# Drone.net
KiCad netlist of a schematic drawn in Altium Designer
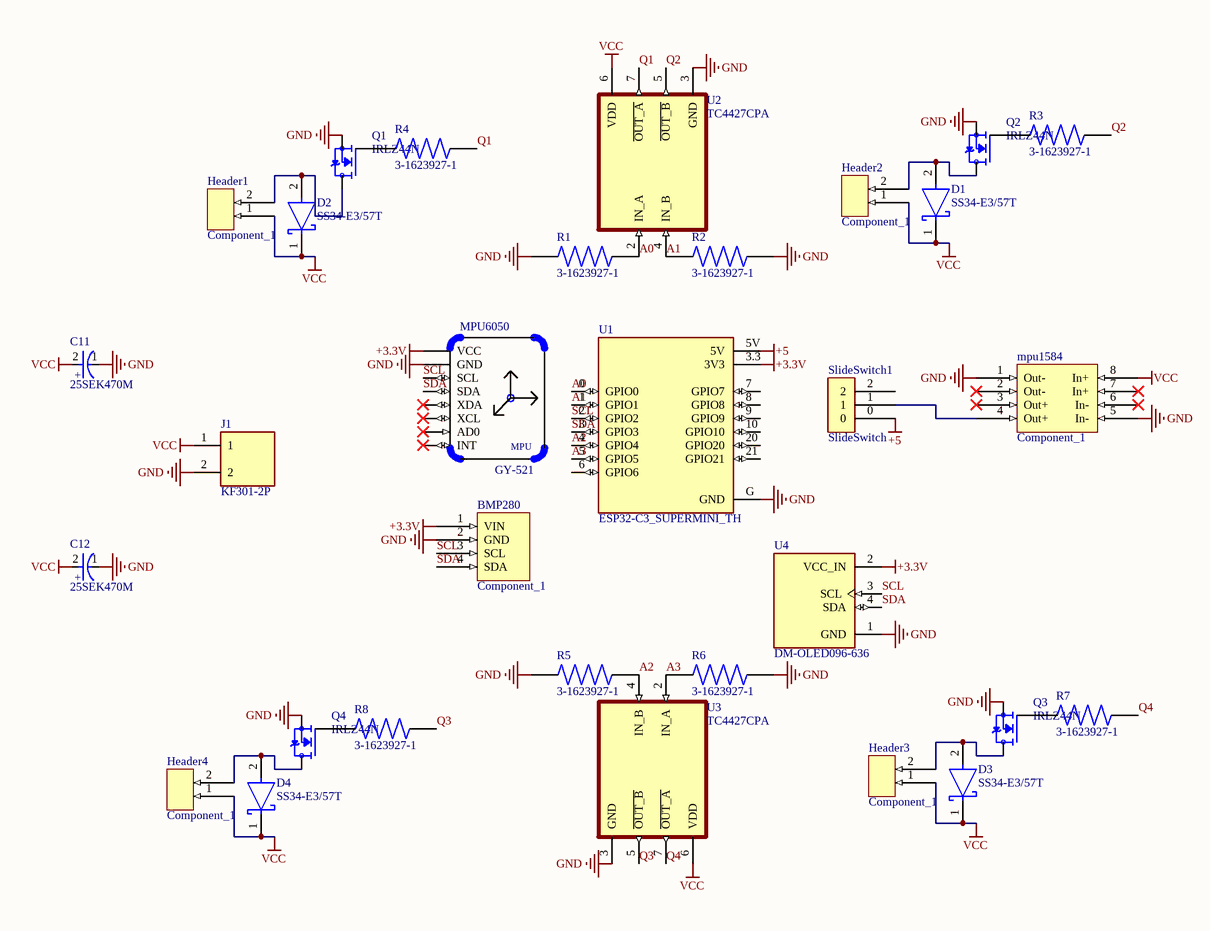
[diagram p0: Drone.SchDoc]

(export (version "E")
  (design (tool "Eeschema 10.0.6"))
  (components
    (comp (ref "BMP280")
      (value "Component_1")
      (footprint "PCBComponent_1")
      (libsource (lib "BMP280_4Pin_5V") (part "Component_1"))
    )
    (comp (ref "C11")
      (value "25SEK470M")
      (footprint "FP-OS-CON-TH-F13-d_0_6-MFG")
      (description "Conductive Polymer Aluminum Solid Capacitors (OS-CON) 470uF ±20% 25V RADIAL TH 10x13mm")
      (libsource (lib "470uF_aluminum") (part "CMP-05428-000411-1"))
    )
    (comp (ref "C12")
      (value "25SEK470M")
      (footprint "FP-OS-CON-TH-F13-d_0_6-MFG")
      (description "Conductive Polymer Aluminum Solid Capacitors (OS-CON) 470uF ±20% 25V RADIAL TH 10x13mm")
      (libsource (lib "470uF_aluminum") (part "CMP-05428-000411-1"))
    )
    (comp (ref "D1")
      (value "SS34-E3/57T")
      (footprint "FP-95402-MFG")
      (description "DIODE SCHOTTKY 40V 3A DO214AB")
      (fields
        (field (name "MANUFACTURER") "Vishay")
        (field (name "OCTOPART") "https://octopart.com/ss34-e3%2F57t-vishay-39552907")
      )
      (libsource (lib "SS34") (part "CMP-02539-000012-1"))
    )
    (comp (ref "D2")
      (value "SS34-E3/57T")
      (footprint "FP-95402-MFG")
      (description "DIODE SCHOTTKY 40V 3A DO214AB")
      (fields
        (field (name "MANUFACTURER") "Vishay")
        (field (name "OCTOPART") "https://octopart.com/ss34-e3%2F57t-vishay-39552907")
      )
      (libsource (lib "SS34") (part "CMP-02539-000012-1"))
    )
    (comp (ref "D3")
      (value "SS34-E3/57T")
      (footprint "FP-95402-MFG")
      (description "DIODE SCHOTTKY 40V 3A DO214AB")
      (fields
        (field (name "MANUFACTURER") "Vishay")
        (field (name "OCTOPART") "https://octopart.com/ss34-e3%2F57t-vishay-39552907")
      )
      (libsource (lib "SS34") (part "CMP-02539-000012-1"))
    )
    (comp (ref "D4")
      (value "SS34-E3/57T")
      (footprint "FP-95402-MFG")
      (description "DIODE SCHOTTKY 40V 3A DO214AB")
      (fields
        (field (name "MANUFACTURER") "Vishay")
        (field (name "OCTOPART") "https://octopart.com/ss34-e3%2F57t-vishay-39552907")
      )
      (libsource (lib "SS34") (part "CMP-02539-000012-1"))
    )
    (comp (ref "Header1")
      (value "Component_1")
      (footprint "1X2P")
      (libsource (lib "1X2P") (part "Component_1"))
    )
    (comp (ref "Header2")
      (value "Component_1")
      (footprint "1X2P")
      (libsource (lib "1X2P") (part "Component_1"))
    )
    (comp (ref "Header3")
      (value "Component_1")
      (footprint "1X2P")
      (libsource (lib "1X2P") (part "Component_1"))
    )
    (comp (ref "Header4")
      (value "Component_1")
      (footprint "1X2P")
      (libsource (lib "1X2P") (part "Component_1"))
    )
    (comp (ref "J1")
      (value "KF301-2P")
      (footprint "HANDSON_KF301-2P")
      (description "2 Pin Terminal Block 5mm Pitch")
      (fields (field (name "MF") "Handson Technology"))
      (libsource (lib "Header_2_foot") (part "KF301-2P"))
    )
    (comp (ref "mpu1584")
      (value "Component_1")
      (footprint "PCBComponent_1")
      (libsource (lib "mpu1584_module") (part "Component_1"))
    )
    (comp (ref "MPU6050")
      (value "GY-521")
      (footprint "*GY-521_GY-521(Primary)")
      (description "Triple Axis Accelerometer Gyro Breakout")
      (fields (field (name "MF") "GODREAM FORDREAM CO., LIMITED"))
      (libsource (lib "GY-521") (part "GY-521"))
    )
    (comp (ref "Q1")
      (value "IRLZ44N")
      (footprint "TO254P1054X469X1930-3")
      (description "N-Channel 55 V 47A (Tc) 3.8W (Ta), 110W (Tc) Surface Mount D2PAK")
      (fields (field (name "MF") "Infineon / IR"))
      (libsource (lib "IRLZ44N") (part "IRLZ44N"))
    )
    (comp (ref "Q2")
      (value "IRLZ44N")
      (footprint "TO254P1054X469X1930-3")
      (description "N-Channel 55 V 47A (Tc) 3.8W (Ta), 110W (Tc) Surface Mount D2PAK")
      (fields (field (name "MF") "Infineon / IR"))
      (libsource (lib "IRLZ44N") (part "IRLZ44N"))
    )
    (comp (ref "Q3")
      (value "IRLZ44N")
      (footprint "TO254P1054X469X1930-3")
      (description "N-Channel 55 V 47A (Tc) 3.8W (Ta), 110W (Tc) Surface Mount D2PAK")
      (fields (field (name "MF") "Infineon / IR"))
      (libsource (lib "IRLZ44N") (part "IRLZ44N"))
    )
    (comp (ref "Q4")
      (value "IRLZ44N")
      (footprint "TO254P1054X469X1930-3")
      (description "N-Channel 55 V 47A (Tc) 3.8W (Ta), 110W (Tc) Surface Mount D2PAK")
      (fields (field (name "MF") "Infineon / IR"))
      (libsource (lib "IRLZ44N") (part "IRLZ44N"))
    )
    (comp (ref "R1")
      (value "3-1623927-1")
      (footprint "RESAD700W45L350D185")
      (description "1 MOhms Â±5% 0.25W, 1/4W Through Hole Resistor Axial - Carbon Film")
      (fields (field (name "MF") "TE Connectivity"))
      (libsource (lib "3-1623927-1-res-plug") (part "3-1623927-1"))
    )
    (comp (ref "R2")
      (value "3-1623927-1")
      (footprint "RESAD700W45L350D185")
      (description "1 MOhms Â±5% 0.25W, 1/4W Through Hole Resistor Axial - Carbon Film")
      (fields (field (name "MF") "TE Connectivity"))
      (libsource (lib "3-1623927-1-res-plug") (part "3-1623927-1"))
    )
    (comp (ref "R3")
      (value "3-1623927-1")
      (footprint "RESAD700W45L350D185")
      (description "1 MOhms Â±5% 0.25W, 1/4W Through Hole Resistor Axial - Carbon Film")
      (fields (field (name "MF") "TE Connectivity"))
      (libsource (lib "3-1623927-1-res-plug") (part "3-1623927-1"))
    )
    (comp (ref "R4")
      (value "3-1623927-1")
      (footprint "RESAD700W45L350D185")
      (description "1 MOhms Â±5% 0.25W, 1/4W Through Hole Resistor Axial - Carbon Film")
      (fields (field (name "MF") "TE Connectivity"))
      (libsource (lib "3-1623927-1-res-plug") (part "3-1623927-1"))
    )
    (comp (ref "R5")
      (value "3-1623927-1")
      (footprint "RESAD700W45L350D185")
      (description "1 MOhms Â±5% 0.25W, 1/4W Through Hole Resistor Axial - Carbon Film")
      (fields (field (name "MF") "TE Connectivity"))
      (libsource (lib "3-1623927-1-res-plug") (part "3-1623927-1"))
    )
    (comp (ref "R6")
      (value "3-1623927-1")
      (footprint "RESAD700W45L350D185")
      (description "1 MOhms Â±5% 0.25W, 1/4W Through Hole Resistor Axial - Carbon Film")
      (fields (field (name "MF") "TE Connectivity"))
      (libsource (lib "3-1623927-1-res-plug") (part "3-1623927-1"))
    )
    (comp (ref "R7")
      (value "3-1623927-1")
      (footprint "RESAD700W45L350D185")
      (description "1 MOhms Â±5% 0.25W, 1/4W Through Hole Resistor Axial - Carbon Film")
      (fields (field (name "MF") "TE Connectivity"))
      (libsource (lib "3-1623927-1-res-plug") (part "3-1623927-1"))
    )
    (comp (ref "R8")
      (value "3-1623927-1")
      (footprint "RESAD700W45L350D185")
      (description "1 MOhms Â±5% 0.25W, 1/4W Through Hole Resistor Axial - Carbon Film")
      (fields (field (name "MF") "TE Connectivity"))
      (libsource (lib "3-1623927-1-res-plug") (part "3-1623927-1"))
    )
    (comp (ref "SlideSwitch1")
      (value "SlideSwitch")
      (footprint "PCBComponent_1")
      (libsource (lib "SlideSwitch") (part "SlideSwitch"))
    )
    (comp (ref "U1")
      (value "ESP32-C3_SUPERMINI_TH")
      (footprint "MODULE_ESP32-C3_SUPERMINI_TH")
      (description "Super tiny ESP32-C3 board")
      (fields (field (name "MF") "Espressif Systems") (field (name "MP") "ESP32-C3 SuperMini_TH"))
      (libsource (lib "ESP32-C3_SUPERMINI_TH") (part "ESP32-C3_SUPERMINI_TH"))
    )
    (comp (ref "U2")
      (value "TC4427CPA")
      (footprint "DIP794W46P254L978H432Q8")
      (fields (field (name "MF") "Microchip Technology"))
      (libsource (lib "TC4427CPA") (part "TC4427CPA"))
    )
    (comp (ref "U3")
      (value "TC4427CPA")
      (footprint "DIP794W46P254L978H432Q8")
      (fields (field (name "MF") "Microchip Technology"))
      (libsource (lib "") (part "TC4427CPA_1"))
    )
    (comp (ref "U4")
      (value "DM-OLED096-636")
      (footprint "MODULE_DM-OLED096-636")
      (description "0.96â€ 128 X 64 MONOCHROME GRAPHIC OLED DISPLAY MODULE - I2C")
      (fields (field (name "MF") "Display Module"))
      (libsource (lib "DM-OLED096-636") (part "DM-OLED096-636"))
    )
  )
  (nets
    (net (code "1") (name "+3.3V") (class "Default")
      (node (ref "BMP280") (pin "1") (pinfunction "VIN_1") (pintype "input"))
      (node (ref "MPU6050") (pin "VCC") (pinfunction "VCC_VCC") (pintype "power_in"))
      (node (ref "U1") (pin "3.3") (pinfunction "3V3_3.3") (pintype "power_in"))
      (node (ref "U4") (pin "2") (pinfunction "VCC_IN_2") (pintype "power_in"))
    )
    (net (code "2") (name "+5") (class "Default")
      (node (ref "SlideSwitch1") (pin "0") (pinfunction "0_0") (pintype "passive"))
      (node (ref "U1") (pin "5V") (pinfunction "5V_5V") (pintype "power_in"))
    )
    (net (code "3") (name "/A0") (class "Default")
      (node (ref "R1") (pin "2") (pinfunction "2_2") (pintype "passive"))
      (node (ref "U1") (pin "0") (pinfunction "GPIO0_0") (pintype "bidirectional"))
      (node (ref "U2") (pin "2") (pinfunction "IN_A_2") (pintype "input"))
    )
    (net (code "4") (name "/A1") (class "Default")
      (node (ref "R2") (pin "1") (pinfunction "1_1") (pintype "passive"))
      (node (ref "U1") (pin "1") (pinfunction "GPIO1_1") (pintype "bidirectional"))
      (node (ref "U2") (pin "4") (pinfunction "IN_B_4") (pintype "input"))
    )
    (net (code "5") (name "/A2") (class "Default")
      (node (ref "R5") (pin "2") (pinfunction "2_2") (pintype "passive"))
      (node (ref "U1") (pin "4") (pinfunction "GPIO4_4") (pintype "bidirectional"))
      (node (ref "U3") (pin "4") (pinfunction "IN_B_4") (pintype "input"))
    )
    (net (code "6") (name "/A3") (class "Default")
      (node (ref "R6") (pin "1") (pinfunction "1_1") (pintype "passive"))
      (node (ref "U1") (pin "5") (pinfunction "GPIO5_5") (pintype "bidirectional"))
      (node (ref "U3") (pin "2") (pinfunction "IN_A_2") (pintype "input"))
    )
    (net (code "7") (name "/Q1") (class "Default")
      (node (ref "R4") (pin "2") (pinfunction "2_2") (pintype "passive"))
      (node (ref "U2") (pin "7") (pinfunction "~{OUT_A}_7") (pintype "output"))
    )
    (net (code "8") (name "/Q2") (class "Default")
      (node (ref "R3") (pin "2") (pinfunction "2_2") (pintype "passive"))
      (node (ref "U2") (pin "5") (pinfunction "~{OUT_B}_5") (pintype "output"))
    )
    (net (code "9") (name "/Q3") (class "Default")
      (node (ref "R8") (pin "2") (pinfunction "2_2") (pintype "passive"))
      (node (ref "U3") (pin "5") (pinfunction "~{OUT_B}_5") (pintype "output"))
    )
    (net (code "10") (name "/Q4") (class "Default")
      (node (ref "R7") (pin "2") (pinfunction "2_2") (pintype "passive"))
      (node (ref "U3") (pin "7") (pinfunction "~{OUT_A}_7") (pintype "output"))
    )
    (net (code "11") (name "/SCL") (class "Default")
      (node (ref "BMP280") (pin "3") (pinfunction "SCL_3") (pintype "input"))
      (node (ref "MPU6050") (pin "SCL") (pinfunction "SCL_SCL") (pintype "bidirectional"))
      (node (ref "U1") (pin "2") (pinfunction "GPIO2_2") (pintype "bidirectional"))
      (node (ref "U4") (pin "3") (pinfunction "SCL_3") (pintype "input"))
    )
    (net (code "12") (name "/SDA") (class "Default")
      (node (ref "BMP280") (pin "4") (pinfunction "SDA_4") (pintype "input"))
      (node (ref "MPU6050") (pin "SDA") (pinfunction "SDA_SDA") (pintype "bidirectional"))
      (node (ref "U1") (pin "3") (pinfunction "GPIO3_3") (pintype "bidirectional"))
      (node (ref "U4") (pin "4") (pinfunction "SDA_4") (pintype "bidirectional"))
    )
    (net (code "13") (name "GND") (class "Default")
      (node (ref "BMP280") (pin "2") (pinfunction "GND_2") (pintype "input"))
      (node (ref "C11") (pin "1") (pinfunction "C_1") (pintype "passive"))
      (node (ref "C12") (pin "1") (pinfunction "C_1") (pintype "passive"))
      (node (ref "J1") (pin "2") (pinfunction "2_2") (pintype "passive"))
      (node (ref "MPU6050") (pin "GND") (pinfunction "GND_GND") (pintype "power_in"))
      (node (ref "Q1") (pin "3") (pinfunction "S_3") (pintype "passive"))
      (node (ref "Q2") (pin "3") (pinfunction "S_3") (pintype "passive"))
      (node (ref "Q3") (pin "3") (pinfunction "S_3") (pintype "passive"))
      (node (ref "Q4") (pin "3") (pinfunction "S_3") (pintype "passive"))
      (node (ref "R1") (pin "1") (pinfunction "1_1") (pintype "passive"))
      (node (ref "R2") (pin "2") (pinfunction "2_2") (pintype "passive"))
      (node (ref "R5") (pin "1") (pinfunction "1_1") (pintype "passive"))
      (node (ref "R6") (pin "2") (pinfunction "2_2") (pintype "passive"))
      (node (ref "U1") (pin "G") (pinfunction "GND_G") (pintype "power_in"))
      (node (ref "U2") (pin "3") (pinfunction "GND_3") (pintype "power_in"))
      (node (ref "U3") (pin "3") (pinfunction "GND_3") (pintype "power_in"))
      (node (ref "U4") (pin "1") (pinfunction "GND_1") (pintype "power_in"))
      (node (ref "mpu1584") (pin "1") (pinfunction "Out-_1") (pintype "input"))
      (node (ref "mpu1584") (pin "5") (pinfunction "In-_5") (pintype "input"))
    )
    (net (code "14") (name "Net-(D1-A)") (class "Default")
      (node (ref "D1") (pin "2") (pinfunction "A_2") (pintype "passive"))
      (node (ref "Header2") (pin "2") (pintype "input"))
      (node (ref "Q2") (pin "2") (pinfunction "D_2") (pintype "passive"))
    )
    (net (code "15") (name "Net-(D2-A)") (class "Default")
      (node (ref "D2") (pin "2") (pinfunction "A_2") (pintype "passive"))
      (node (ref "Header1") (pin "2") (pintype "input"))
      (node (ref "Q1") (pin "2") (pinfunction "D_2") (pintype "passive"))
    )
    (net (code "16") (name "Net-(D3-A)") (class "Default")
      (node (ref "D3") (pin "2") (pinfunction "A_2") (pintype "passive"))
      (node (ref "Header3") (pin "2") (pintype "input"))
      (node (ref "Q3") (pin "2") (pinfunction "D_2") (pintype "passive"))
    )
    (net (code "17") (name "Net-(D4-A)") (class "Default")
      (node (ref "D4") (pin "2") (pinfunction "A_2") (pintype "passive"))
      (node (ref "Header4") (pin "2") (pintype "input"))
      (node (ref "Q4") (pin "2") (pinfunction "D_2") (pintype "passive"))
    )
    (net (code "18") (name "Net-(Q1-G)") (class "Default")
      (node (ref "Q1") (pin "1") (pinfunction "G_1") (pintype "passive"))
      (node (ref "R4") (pin "1") (pinfunction "1_1") (pintype "passive"))
    )
    (net (code "19") (name "Net-(Q2-G)") (class "Default")
      (node (ref "Q2") (pin "1") (pinfunction "G_1") (pintype "passive"))
      (node (ref "R3") (pin "1") (pinfunction "1_1") (pintype "passive"))
    )
    (net (code "20") (name "Net-(Q3-G)") (class "Default")
      (node (ref "Q3") (pin "1") (pinfunction "G_1") (pintype "passive"))
      (node (ref "R7") (pin "1") (pinfunction "1_1") (pintype "passive"))
    )
    (net (code "21") (name "Net-(Q4-G)") (class "Default")
      (node (ref "Q4") (pin "1") (pinfunction "G_1") (pintype "passive"))
      (node (ref "R8") (pin "1") (pinfunction "1_1") (pintype "passive"))
    )
    (net (code "22") (name "Net-(SlideSwitch1-Pad1)") (class "Default")
      (node (ref "SlideSwitch1") (pin "1") (pinfunction "1_1") (pintype "passive"))
      (node (ref "mpu1584") (pin "4") (pinfunction "Out+_4") (pintype "input"))
    )
    (net (code "23") (name "VCC") (class "Default")
      (node (ref "C11") (pin "2") (pinfunction "A_2") (pintype "passive"))
      (node (ref "C12") (pin "2") (pinfunction "A_2") (pintype "passive"))
      (node (ref "D1") (pin "1") (pinfunction "C_1") (pintype "passive"))
      (node (ref "D2") (pin "1") (pinfunction "C_1") (pintype "passive"))
      (node (ref "D3") (pin "1") (pinfunction "C_1") (pintype "passive"))
      (node (ref "D4") (pin "1") (pinfunction "C_1") (pintype "passive"))
      (node (ref "Header1") (pin "1") (pintype "input"))
      (node (ref "Header2") (pin "1") (pintype "input"))
      (node (ref "Header3") (pin "1") (pintype "input"))
      (node (ref "Header4") (pin "1") (pintype "input"))
      (node (ref "J1") (pin "1") (pinfunction "1_1") (pintype "passive"))
      (node (ref "U2") (pin "6") (pinfunction "VDD_6") (pintype "power_in"))
      (node (ref "U3") (pin "6") (pinfunction "VDD_6") (pintype "power_in"))
      (node (ref "mpu1584") (pin "8") (pinfunction "In+_8") (pintype "input"))
    )
    (net (code "24") (name "unconnected-(MPU6050-PadAD0)") (class "Default")
      (node (ref "MPU6050") (pin "AD0") (pinfunction "AD0_AD0") (pintype "input+no_connect"))
    )
    (net (code "25") (name "unconnected-(MPU6050-PadINT)") (class "Default")
      (node (ref "MPU6050") (pin "INT") (pinfunction "INT_INT") (pintype "bidirectional+no_connect"))
    )
    (net (code "26") (name "unconnected-(MPU6050-PadXCL)") (class "Default")
      (node (ref "MPU6050") (pin "XCL") (pinfunction "XCL_XCL") (pintype "bidirectional+no_connect"))
    )
    (net (code "27") (name "unconnected-(MPU6050-PadXDA)") (class "Default")
      (node (ref "MPU6050") (pin "XDA") (pinfunction "XDA_XDA") (pintype "bidirectional+no_connect"))
    )
    (net (code "28") (name "unconnected-(SlideSwitch1-Pad2)") (class "Default")
      (node (ref "SlideSwitch1") (pin "2") (pinfunction "2_2") (pintype "passive"))
    )
    (net (code "29") (name "unconnected-(U1-GPIO6-Pad6)") (class "Default")
      (node (ref "U1") (pin "6") (pinfunction "GPIO6_6") (pintype "bidirectional"))
    )
    (net (code "30") (name "unconnected-(U1-GPIO7-Pad7)") (class "Default")
      (node (ref "U1") (pin "7") (pinfunction "GPIO7_7") (pintype "bidirectional"))
    )
    (net (code "31") (name "unconnected-(U1-GPIO8-Pad8)") (class "Default")
      (node (ref "U1") (pin "8") (pinfunction "GPIO8_8") (pintype "bidirectional"))
    )
    (net (code "32") (name "unconnected-(U1-GPIO9-Pad9)") (class "Default")
      (node (ref "U1") (pin "9") (pinfunction "GPIO9_9") (pintype "bidirectional"))
    )
    (net (code "33") (name "unconnected-(U1-GPIO10-Pad10)") (class "Default")
      (node (ref "U1") (pin "10") (pinfunction "GPIO10_10") (pintype "bidirectional"))
    )
    (net (code "34") (name "unconnected-(U1-GPIO20-Pad20)") (class "Default")
      (node (ref "U1") (pin "20") (pinfunction "GPIO20_20") (pintype "bidirectional"))
    )
    (net (code "35") (name "unconnected-(U1-GPIO21-Pad21)") (class "Default")
      (node (ref "U1") (pin "21") (pinfunction "GPIO21_21") (pintype "bidirectional"))
    )
    (net (code "36") (name "unconnected-(mpu1584-In+-Pad7)") (class "Default")
      (node (ref "mpu1584") (pin "7") (pinfunction "In+_7") (pintype "input+no_connect"))
    )
    (net (code "37") (name "unconnected-(mpu1584-In--Pad6)") (class "Default")
      (node (ref "mpu1584") (pin "6") (pinfunction "In-_6") (pintype "input+no_connect"))
    )
    (net (code "38") (name "unconnected-(mpu1584-Out+-Pad3)") (class "Default")
      (node (ref "mpu1584") (pin "3") (pinfunction "Out+_3") (pintype "input+no_connect"))
    )
    (net (code "39") (name "unconnected-(mpu1584-Out--Pad2)") (class "Default")
      (node (ref "mpu1584") (pin "2") (pinfunction "Out-_2") (pintype "input+no_connect"))
    )
  )
)
